# BackupPowerSupply.net
KiCad netlist of a schematic drawn in EAGLE
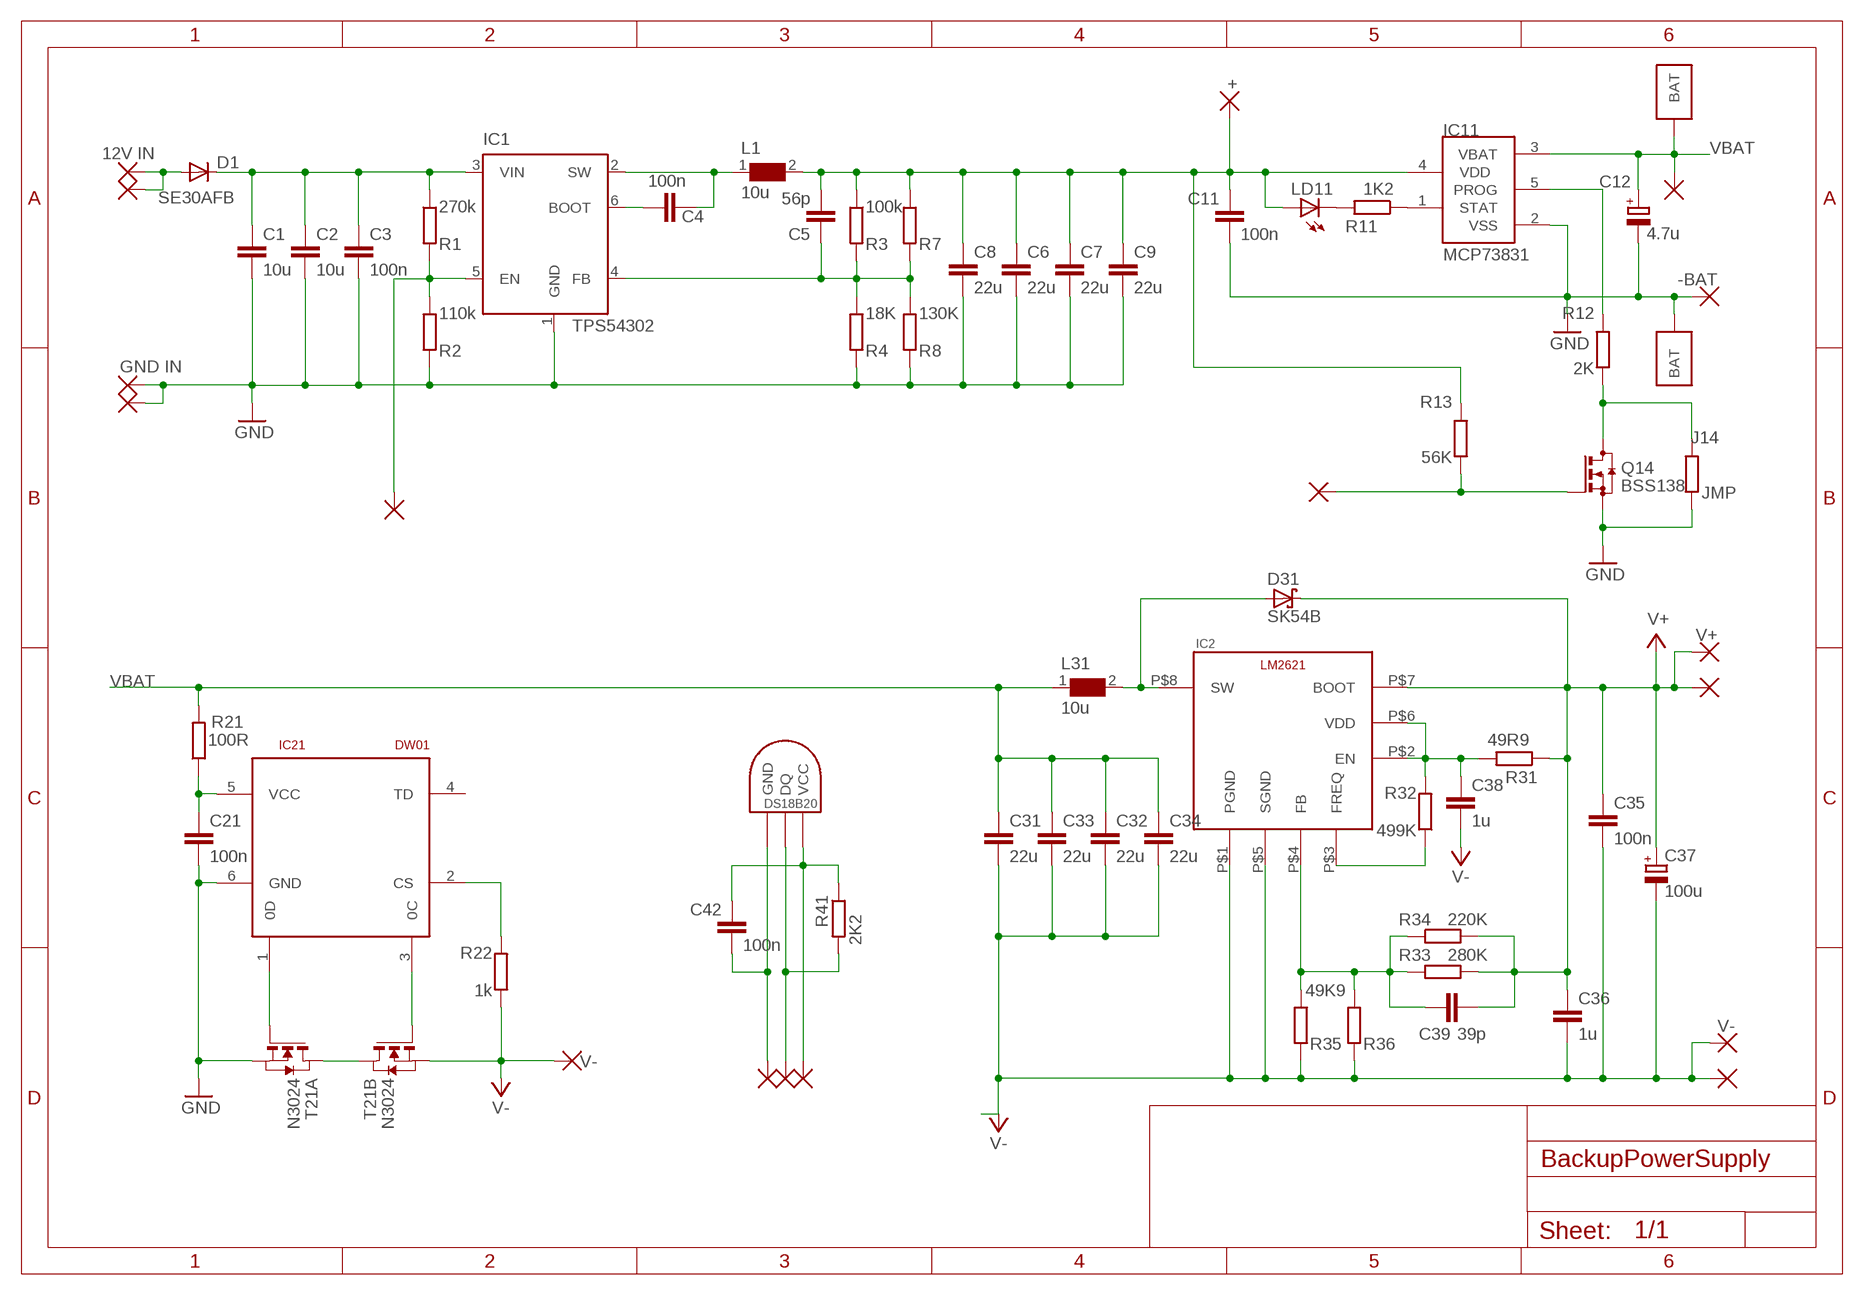
[diagram p0: schematic, sheet 1]

(export (version "E")
  (design (tool "Eeschema 10.0.6"))
  (components
    (comp (ref "C1")
      (value "10u")
      (footprint "eagle-import:C1206")
      (libsource (lib "eagle-import") (part "C-EUC1206"))
    )
    (comp (ref "C2")
      (value "10u")
      (footprint "eagle-import:C1206")
      (libsource (lib "eagle-import") (part "C-EUC1206"))
    )
    (comp (ref "C3")
      (value "100n")
      (footprint "eagle-import:C1206")
      (libsource (lib "eagle-import") (part "C-EUC1206"))
    )
    (comp (ref "C4")
      (value "100n")
      (footprint "eagle-import:C0805")
      (libsource (lib "eagle-import") (part "C-EUC0805"))
    )
    (comp (ref "C5")
      (value "56p")
      (footprint "eagle-import:C0805")
      (libsource (lib "eagle-import") (part "C-EUC0805"))
    )
    (comp (ref "C6")
      (value "22u")
      (footprint "eagle-import:C0805")
      (libsource (lib "eagle-import") (part "C-EUC0805"))
    )
    (comp (ref "C7")
      (value "22u")
      (footprint "eagle-import:C0805")
      (libsource (lib "eagle-import") (part "C-EUC0805"))
    )
    (comp (ref "C8")
      (value "22u")
      (footprint "eagle-import:C0805")
      (libsource (lib "eagle-import") (part "C-EUC0805"))
    )
    (comp (ref "C9")
      (value "22u")
      (footprint "eagle-import:C0805")
      (libsource (lib "eagle-import") (part "C-EUC0805"))
    )
    (comp (ref "C11")
      (value "100n")
      (footprint "eagle-import:C0805")
      (libsource (lib "eagle-import") (part "C-EUC0805"))
    )
    (comp (ref "C12")
      (value "4.7u")
      (footprint "eagle-import:SMC_A")
      (libsource (lib "eagle-import") (part "CPOL-EUSMCA"))
    )
    (comp (ref "C21")
      (value "100n")
      (footprint "eagle-import:C0805")
      (libsource (lib "eagle-import") (part "C-EUC0805"))
    )
    (comp (ref "C31")
      (value "22u")
      (footprint "eagle-import:C0805")
      (libsource (lib "eagle-import") (part "C-EUC0805"))
    )
    (comp (ref "C32")
      (value "22u")
      (footprint "eagle-import:C0805")
      (libsource (lib "eagle-import") (part "C-EUC0805"))
    )
    (comp (ref "C33")
      (value "22u")
      (footprint "eagle-import:C0805")
      (libsource (lib "eagle-import") (part "C-EUC0805"))
    )
    (comp (ref "C34")
      (value "22u")
      (footprint "eagle-import:C0805")
      (libsource (lib "eagle-import") (part "C-EUC0805"))
    )
    (comp (ref "C35")
      (value "100n")
      (footprint "eagle-import:C0805")
      (libsource (lib "eagle-import") (part "C-EUC0805"))
    )
    (comp (ref "C36")
      (value "1u")
      (footprint "eagle-import:C0805")
      (libsource (lib "eagle-import") (part "C-EUC0805"))
    )
    (comp (ref "C37")
      (value "100u")
      (footprint "eagle-import:SMC_B")
      (libsource (lib "eagle-import") (part "CPOL-EUSMCB"))
    )
    (comp (ref "C38")
      (value "1u")
      (footprint "eagle-import:C0805")
      (libsource (lib "eagle-import") (part "C-EUC0805"))
    )
    (comp (ref "C39")
      (value "39p")
      (footprint "eagle-import:C0805")
      (libsource (lib "eagle-import") (part "C-EUC0805"))
    )
    (comp (ref "C42")
      (value "100n")
      (footprint "eagle-import:C0603")
      (libsource (lib "eagle-import") (part "C-EUC0603"))
    )
    (comp (ref "D1")
      (value "SE30AFB")
      (footprint "eagle-import:SOD-123_MINI-SMA")
      (libsource (lib "eagle-import") (part "CGRM400-G1"))
    )
    (comp (ref "D31")
      (value "SK54B")
      (footprint "eagle-import:SMB")
      (libsource (lib "eagle-import") (part "SCHOTTKY-DIODESMD"))
    )
    (comp (ref "DS18B20")
      (value "DS1820SOIC")
      (footprint "eagle-import:DS18B20_SOIC")
      (libsource (lib "eagle-import") (part "DS1820SOIC"))
    )
    (comp (ref "IC1")
      (value "TPS54302")
      (footprint "eagle-import:TSOT23-6_DDC")
      (libsource (lib "eagle-import") (part "TPS54302"))
    )
    (comp (ref "IC2")
      (value "LM2621VSSOP8")
      (footprint "eagle-import:VSSOP8")
      (libsource (lib "eagle-import") (part "LM2621VSSOP8"))
    )
    (comp (ref "IC11")
      (value "MCP73831")
      (footprint "eagle-import:SOT23-5L")
      (libsource (lib "eagle-import") (part "MCP73831"))
    )
    (comp (ref "IC21")
      (value "DW01")
      (footprint "eagle-import:SOT23-6")
      (libsource (lib "eagle-import") (part "DW01"))
    )
    (comp (ref "J14")
      (value "JMP")
      (footprint "eagle-import:R0201")
      (libsource (lib "eagle-import") (part "R-EU_R0201"))
    )
    (comp (ref "L1")
      (value "10u")
      (footprint "eagle-import:WE-LQS_8040")
      (libsource (lib "eagle-import") (part "WE-LQS_8040"))
    )
    (comp (ref "L31")
      (value "10u")
      (footprint "eagle-import:WE-LQS_8040")
      (libsource (lib "eagle-import") (part "WE-LQS_8040"))
    )
    (comp (ref "LD11")
      (value "LEDCHIPLED_0805")
      (footprint "eagle-import:CHIPLED_0805")
      (libsource (lib "eagle-import") (part "LEDCHIPLED_0805"))
    )
    (comp (ref "PAD1")
      (value "+BAT")
      (footprint "eagle-import:PAD")
      (libsource (lib "eagle-import") (part "PAD"))
    )
    (comp (ref "PAD2")
      (value "-BAT")
      (footprint "eagle-import:PAD")
      (libsource (lib "eagle-import") (part "PAD"))
    )
    (comp (ref "PAD3")
      (value "12V IN")
      (footprint "eagle-import:PAD")
      (libsource (lib "eagle-import") (part "PAD"))
    )
    (comp (ref "PAD4")
      (value "GND IN")
      (footprint "eagle-import:PAD")
      (libsource (lib "eagle-import") (part "PAD"))
    )
    (comp (ref "PAD5")
      (value "V+")
      (footprint "eagle-import:PAD")
      (libsource (lib "eagle-import") (part "PAD"))
    )
    (comp (ref "PAD6")
      (value "V-")
      (footprint "eagle-import:PAD")
      (libsource (lib "eagle-import") (part "PAD"))
    )
    (comp (ref "PAD7")
      (value "+")
      (footprint "eagle-import:PAD")
      (libsource (lib "eagle-import") (part "PAD"))
    )
    (comp (ref "PAD8")
      (value "PAD")
      (footprint "eagle-import:PAD")
      (libsource (lib "eagle-import") (part "PAD"))
    )
    (comp (ref "PAD9")
      (value "V-")
      (footprint "eagle-import:PAD")
      (libsource (lib "eagle-import") (part "PAD"))
    )
    (comp (ref "PAD11")
      (value "V-")
      (footprint "eagle-import:PAD")
      (libsource (lib "eagle-import") (part "PAD"))
    )
    (comp (ref "PAD12")
      (value "V+")
      (footprint "eagle-import:PAD")
      (libsource (lib "eagle-import") (part "PAD"))
    )
    (comp (ref "PAD13")
      (value "+")
      (footprint "eagle-import:PAD")
      (libsource (lib "eagle-import") (part "PAD"))
    )
    (comp (ref "PAD19")
      (value "V-")
      (footprint "eagle-import:PAD")
      (libsource (lib "eagle-import") (part "PAD"))
    )
    (comp (ref "PAD20")
      (value "V-")
      (footprint "eagle-import:PAD")
      (libsource (lib "eagle-import") (part "PAD"))
    )
    (comp (ref "PAD21")
      (value "V-")
      (footprint "eagle-import:PAD")
      (libsource (lib "eagle-import") (part "PAD"))
    )
    (comp (ref "PAD22")
      (value "PAD")
      (footprint "eagle-import:PAD")
      (libsource (lib "eagle-import") (part "PAD"))
    )
    (comp (ref "Q14")
      (value "BSS138")
      (footprint "eagle-import:SOT23")
      (libsource (lib "eagle-import") (part "BSS123"))
    )
    (comp (ref "R1")
      (value "270k")
      (footprint "eagle-import:M0805")
      (libsource (lib "eagle-import") (part "R-EU_M0805"))
    )
    (comp (ref "R2")
      (value "110k")
      (footprint "eagle-import:M0805")
      (libsource (lib "eagle-import") (part "R-EU_M0805"))
    )
    (comp (ref "R3")
      (value "100k")
      (footprint "eagle-import:M0805")
      (libsource (lib "eagle-import") (part "R-EU_M0805"))
    )
    (comp (ref "R4")
      (value "18K")
      (footprint "eagle-import:M0805")
      (libsource (lib "eagle-import") (part "R-EU_M0805"))
    )
    (comp (ref "R7")
      (value "R-EU_M0805")
      (footprint "eagle-import:M0805")
      (libsource (lib "eagle-import") (part "R-EU_M0805"))
    )
    (comp (ref "R8")
      (value "130K")
      (footprint "eagle-import:M0805")
      (libsource (lib "eagle-import") (part "R-EU_M0805"))
    )
    (comp (ref "R11")
      (value "1K2")
      (footprint "eagle-import:M0805")
      (libsource (lib "eagle-import") (part "R-EU_M0805"))
    )
    (comp (ref "R12")
      (value "2K")
      (footprint "eagle-import:M0805")
      (libsource (lib "eagle-import") (part "R-EU_M0805"))
    )
    (comp (ref "R13")
      (value "56K")
      (footprint "eagle-import:M0805")
      (libsource (lib "eagle-import") (part "R-EU_M0805"))
    )
    (comp (ref "R21")
      (value "100R")
      (footprint "eagle-import:M0805")
      (libsource (lib "eagle-import") (part "R-EU_M0805"))
    )
    (comp (ref "R22")
      (value "1k")
      (footprint "eagle-import:M0805")
      (libsource (lib "eagle-import") (part "R-EU_M0805"))
    )
    (comp (ref "R31")
      (value "49R9")
      (footprint "eagle-import:M0805")
      (libsource (lib "eagle-import") (part "R-EU_M0805"))
    )
    (comp (ref "R32")
      (value "499K")
      (footprint "eagle-import:M0805")
      (libsource (lib "eagle-import") (part "R-EU_M0805"))
    )
    (comp (ref "R33")
      (value "280K")
      (footprint "eagle-import:M0805")
      (libsource (lib "eagle-import") (part "R-EU_M0805"))
    )
    (comp (ref "R34")
      (value "220K")
      (footprint "eagle-import:M0805")
      (libsource (lib "eagle-import") (part "R-EU_M0805"))
    )
    (comp (ref "R35")
      (value "49K9")
      (footprint "eagle-import:M0805")
      (libsource (lib "eagle-import") (part "R-EU_M0805"))
    )
    (comp (ref "R36")
      (value "R-EU_M0805")
      (footprint "eagle-import:M0805")
      (libsource (lib "eagle-import") (part "R-EU_M0805"))
    )
    (comp (ref "R41")
      (value "2K2")
      (footprint "eagle-import:R0603")
      (libsource (lib "eagle-import") (part "R-EU_R0603"))
    )
    (comp (ref "T21")
      (value "N3024")
      (footprint "eagle-import:TSSOP-8")
      (libsource (lib "eagle-import") (part "DMN3024LSD"))
    )
    (comp (ref "U$1")
      (value "BAT_A")
      (footprint "eagle-import:BAT_A")
      (libsource (lib "eagle-import") (part "BAT_A"))
    )
    (comp (ref "U$2")
      (value "BAT_A")
      (footprint "eagle-import:BAT_A")
      (libsource (lib "eagle-import") (part "BAT_A"))
    )
    (comp (ref "U$3")
      (value "PAD")
      (footprint "eagle-import:PAD")
      (libsource (lib "eagle-import") (part "PAD"))
    )
  )
  (nets
    (net (code "1") (name "/VBAT") (class "Default")
      (node (ref "C12") (pin "+") (pinfunction "+_+") (pintype "passive"))
      (node (ref "C31") (pin "2") (pinfunction "2_2") (pintype "passive"))
      (node (ref "C32") (pin "2") (pinfunction "2_2") (pintype "passive"))
      (node (ref "C33") (pin "2") (pinfunction "2_2") (pintype "passive"))
      (node (ref "C34") (pin "2") (pinfunction "2_2") (pintype "passive"))
      (node (ref "IC11") (pin "3") (pinfunction "VBAT_3") (pintype "bidirectional"))
      (node (ref "L31") (pin "1") (pinfunction "1_1") (pintype "passive"))
      (node (ref "PAD1") (pin "P$1") (pinfunction "P$1_P$1") (pintype "bidirectional"))
      (node (ref "R21") (pin "2") (pinfunction "2_2") (pintype "passive"))
      (node (ref "U$1") (pin "P$1") (pinfunction "BAT_P$1") (pintype "power_in"))
      (node (ref "U$1") (pin "P$4") (pinfunction "BAT_P$4") (pintype "power_in"))
    )
    (net (code "2") (name "GND") (class "Default")
      (node (ref "C1") (pin "1") (pinfunction "1_1") (pintype "passive"))
      (node (ref "C11") (pin "1") (pinfunction "1_1") (pintype "passive"))
      (node (ref "C12") (pin "-") (pinfunction "-_-") (pintype "passive"))
      (node (ref "C2") (pin "1") (pinfunction "1_1") (pintype "passive"))
      (node (ref "C21") (pin "1") (pinfunction "1_1") (pintype "passive"))
      (node (ref "C3") (pin "1") (pinfunction "1_1") (pintype "passive"))
      (node (ref "C6") (pin "1") (pinfunction "1_1") (pintype "passive"))
      (node (ref "C7") (pin "1") (pinfunction "1_1") (pintype "passive"))
      (node (ref "C8") (pin "1") (pinfunction "1_1") (pintype "passive"))
      (node (ref "C9") (pin "1") (pinfunction "1_1") (pintype "passive"))
      (node (ref "IC1") (pin "1") (pinfunction "GND_1") (pintype "power_in"))
      (node (ref "IC11") (pin "2") (pinfunction "VSS_2") (pintype "bidirectional"))
      (node (ref "IC21") (pin "6") (pinfunction "GND_6") (pintype "bidirectional"))
      (node (ref "J14") (pin "1") (pinfunction "1_1") (pintype "passive"))
      (node (ref "PAD2") (pin "P$1") (pinfunction "P$1_P$1") (pintype "bidirectional"))
      (node (ref "PAD4") (pin "P$1") (pinfunction "P$1_P$1") (pintype "bidirectional"))
      (node (ref "PAD8") (pin "P$1") (pinfunction "P$1_P$1") (pintype "bidirectional"))
      (node (ref "Q14") (pin "2") (pinfunction "S_2") (pintype "passive"))
      (node (ref "R2") (pin "2") (pinfunction "2_2") (pintype "passive"))
      (node (ref "R4") (pin "2") (pinfunction "2_2") (pintype "passive"))
      (node (ref "R8") (pin "2") (pinfunction "2_2") (pintype "passive"))
      (node (ref "T21") (pin "2") (pinfunction "S_2") (pintype "bidirectional"))
      (node (ref "T21") (pin "3") (pinfunction "S_3") (pintype "bidirectional"))
      (node (ref "U$2") (pin "P$1") (pinfunction "BAT_P$1") (pintype "power_in"))
      (node (ref "U$2") (pin "P$4") (pinfunction "BAT_P$4") (pintype "power_in"))
    )
    (net (code "3") (name "Net-(C42-Pad1)") (class "Default")
      (node (ref "C42") (pin "1") (pinfunction "1_1") (pintype "passive"))
      (node (ref "DS18B20") (pin "GND") (pinfunction "GND_GND") (pintype "power_in"))
      (node (ref "PAD21") (pin "P$1") (pinfunction "P$1_P$1") (pintype "bidirectional"))
    )
    (net (code "4") (name "Net-(C42-Pad2)") (class "Default")
      (node (ref "C42") (pin "2") (pinfunction "2_2") (pintype "passive"))
      (node (ref "DS18B20") (pin "VCC") (pinfunction "VCC_VCC") (pintype "power_in"))
      (node (ref "PAD20") (pin "P$1") (pinfunction "P$1_P$1") (pintype "bidirectional"))
      (node (ref "R41") (pin "1") (pinfunction "1_1") (pintype "passive"))
    )
    (net (code "5") (name "Net-(D1-PadA)") (class "Default")
      (node (ref "D1") (pin "A") (pinfunction "A_A") (pintype "passive"))
      (node (ref "PAD3") (pin "P$1") (pinfunction "P$1_P$1") (pintype "bidirectional"))
      (node (ref "U$3") (pin "P$1") (pinfunction "P$1_P$1") (pintype "bidirectional"))
    )
    (net (code "6") (name "Net-(DS18B20-PadDQ)") (class "Default")
      (node (ref "DS18B20") (pin "DQ") (pinfunction "DQ_DQ") (pintype "bidirectional"))
      (node (ref "PAD19") (pin "P$1") (pinfunction "P$1_P$1") (pintype "bidirectional"))
      (node (ref "R41") (pin "2") (pinfunction "2_2") (pintype "passive"))
    )
    (net (code "7") (name "Net-(IC1-BOOT)") (class "Default")
      (node (ref "C4") (pin "2") (pinfunction "2_2") (pintype "passive"))
      (node (ref "IC1") (pin "6") (pinfunction "BOOT_6") (pintype "output"))
    )
    (net (code "8") (name "Net-(IC1-EN)") (class "Default")
      (node (ref "IC1") (pin "5") (pinfunction "EN_5") (pintype "power_in"))
      (node (ref "PAD22") (pin "P$1") (pinfunction "P$1_P$1") (pintype "bidirectional"))
      (node (ref "R1") (pin "2") (pinfunction "2_2") (pintype "passive"))
      (node (ref "R2") (pin "1") (pinfunction "1_1") (pintype "passive"))
    )
    (net (code "9") (name "Net-(IC1-FB)") (class "Default")
      (node (ref "C5") (pin "2") (pinfunction "2_2") (pintype "passive"))
      (node (ref "IC1") (pin "4") (pinfunction "FB_4") (pintype "input"))
      (node (ref "R3") (pin "2") (pinfunction "2_2") (pintype "passive"))
      (node (ref "R4") (pin "1") (pinfunction "1_1") (pintype "passive"))
      (node (ref "R7") (pin "2") (pinfunction "2_2") (pintype "passive"))
      (node (ref "R8") (pin "1") (pinfunction "1_1") (pintype "passive"))
    )
    (net (code "10") (name "Net-(IC1-SW)") (class "Default")
      (node (ref "C4") (pin "1") (pinfunction "1_1") (pintype "passive"))
      (node (ref "IC1") (pin "2") (pinfunction "SW_2") (pintype "input"))
      (node (ref "L1") (pin "1") (pinfunction "1_1") (pintype "passive"))
    )
    (net (code "11") (name "Net-(IC1-VIN)") (class "Default")
      (node (ref "C1") (pin "2") (pinfunction "2_2") (pintype "passive"))
      (node (ref "C2") (pin "2") (pinfunction "2_2") (pintype "passive"))
      (node (ref "C3") (pin "2") (pinfunction "2_2") (pintype "passive"))
      (node (ref "D1") (pin "C") (pinfunction "C_C") (pintype "passive"))
      (node (ref "IC1") (pin "3") (pinfunction "VIN_3") (pintype "power_in"))
      (node (ref "R1") (pin "1") (pinfunction "1_1") (pintype "passive"))
    )
    (net (code "12") (name "Net-(IC2-EN)") (class "Default")
      (node (ref "C38") (pin "2") (pinfunction "2_2") (pintype "passive"))
      (node (ref "IC2") (pin "P$2") (pinfunction "EN_P$2") (pintype "bidirectional"))
      (node (ref "IC2") (pin "P$6") (pinfunction "VDD_P$6") (pintype "bidirectional"))
      (node (ref "R31") (pin "2") (pinfunction "2_2") (pintype "passive"))
      (node (ref "R32") (pin "2") (pinfunction "2_2") (pintype "passive"))
    )
    (net (code "13") (name "Net-(IC2-FB)") (class "Default")
      (node (ref "C39") (pin "1") (pinfunction "1_1") (pintype "passive"))
      (node (ref "IC2") (pin "P$4") (pinfunction "FB_P$4") (pintype "bidirectional"))
      (node (ref "R33") (pin "1") (pinfunction "1_1") (pintype "passive"))
      (node (ref "R34") (pin "1") (pinfunction "1_1") (pintype "passive"))
      (node (ref "R35") (pin "1") (pinfunction "1_1") (pintype "passive"))
      (node (ref "R36") (pin "1") (pinfunction "1_1") (pintype "passive"))
    )
    (net (code "14") (name "Net-(IC2-FREQ)") (class "Default")
      (node (ref "IC2") (pin "P$3") (pinfunction "FREQ_P$3") (pintype "bidirectional"))
      (node (ref "R32") (pin "1") (pinfunction "1_1") (pintype "passive"))
    )
    (net (code "15") (name "Net-(IC2-SW)") (class "Default")
      (node (ref "D31") (pin "A") (pinfunction "A_A") (pintype "passive"))
      (node (ref "IC2") (pin "P$8") (pinfunction "SW_P$8") (pintype "bidirectional"))
      (node (ref "L31") (pin "2") (pinfunction "2_2") (pintype "passive"))
    )
    (net (code "16") (name "Net-(IC11-PROG)") (class "Default")
      (node (ref "IC11") (pin "5") (pinfunction "PROG_5") (pintype "bidirectional"))
      (node (ref "R12") (pin "2") (pinfunction "2_2") (pintype "passive"))
    )
    (net (code "17") (name "Net-(IC11-STAT)") (class "Default")
      (node (ref "IC11") (pin "1") (pinfunction "STAT_1") (pintype "bidirectional"))
      (node (ref "R11") (pin "1") (pinfunction "1_1") (pintype "passive"))
    )
    (net (code "18") (name "Net-(IC11-VDD)") (class "Default")
      (node (ref "C11") (pin "2") (pinfunction "2_2") (pintype "passive"))
      (node (ref "C5") (pin "1") (pinfunction "1_1") (pintype "passive"))
      (node (ref "C6") (pin "2") (pinfunction "2_2") (pintype "passive"))
      (node (ref "C7") (pin "2") (pinfunction "2_2") (pintype "passive"))
      (node (ref "C8") (pin "2") (pinfunction "2_2") (pintype "passive"))
      (node (ref "C9") (pin "2") (pinfunction "2_2") (pintype "passive"))
      (node (ref "IC11") (pin "4") (pinfunction "VDD_4") (pintype "bidirectional"))
      (node (ref "L1") (pin "2") (pinfunction "2_2") (pintype "passive"))
      (node (ref "LD11") (pin "A") (pinfunction "A_A") (pintype "passive"))
      (node (ref "PAD13") (pin "P$1") (pinfunction "P$1_P$1") (pintype "bidirectional"))
      (node (ref "R13") (pin "2") (pinfunction "2_2") (pintype "passive"))
      (node (ref "R3") (pin "1") (pinfunction "1_1") (pintype "passive"))
      (node (ref "R7") (pin "1") (pinfunction "1_1") (pintype "passive"))
    )
    (net (code "19") (name "Net-(IC21-0C)") (class "Default")
      (node (ref "IC21") (pin "3") (pinfunction "0C_3") (pintype "bidirectional"))
      (node (ref "T21") (pin "5") (pinfunction "G_5") (pintype "bidirectional"))
    )
    (net (code "20") (name "Net-(IC21-0D)") (class "Default")
      (node (ref "IC21") (pin "1") (pinfunction "0D_1") (pintype "bidirectional"))
      (node (ref "T21") (pin "4") (pinfunction "G_4") (pintype "bidirectional"))
    )
    (net (code "21") (name "Net-(IC21-CS)") (class "Default")
      (node (ref "IC21") (pin "2") (pinfunction "CS_2") (pintype "bidirectional"))
      (node (ref "R22") (pin "2") (pinfunction "2_2") (pintype "passive"))
    )
    (net (code "22") (name "Net-(IC21-VCC)") (class "Default")
      (node (ref "C21") (pin "2") (pinfunction "2_2") (pintype "passive"))
      (node (ref "IC21") (pin "5") (pinfunction "VCC_5") (pintype "bidirectional"))
      (node (ref "R21") (pin "1") (pinfunction "1_1") (pintype "passive"))
    )
    (net (code "23") (name "Net-(LD11-PadC)") (class "Default")
      (node (ref "LD11") (pin "C") (pinfunction "C_C") (pintype "passive"))
      (node (ref "R11") (pin "2") (pinfunction "2_2") (pintype "passive"))
    )
    (net (code "24") (name "Net-(Q14-D)") (class "Default")
      (node (ref "J14") (pin "2") (pinfunction "2_2") (pintype "passive"))
      (node (ref "Q14") (pin "3") (pinfunction "D_3") (pintype "passive"))
      (node (ref "R12") (pin "1") (pinfunction "1_1") (pintype "passive"))
    )
    (net (code "25") (name "Net-(Q14-G)") (class "Default")
      (node (ref "PAD7") (pin "P$1") (pinfunction "P$1_P$1") (pintype "bidirectional"))
      (node (ref "Q14") (pin "1") (pinfunction "G_1") (pintype "passive"))
      (node (ref "R13") (pin "1") (pinfunction "1_1") (pintype "passive"))
    )
    (net (code "26") (name "Net-(T21A-D)") (class "Default")
      (node (ref "T21") (pin "1") (pinfunction "D_1") (pintype "bidirectional"))
      (node (ref "T21") (pin "8") (pinfunction "D_8") (pintype "bidirectional"))
    )
    (net (code "27") (name "V+") (class "Default")
      (node (ref "C35") (pin "2") (pinfunction "2_2") (pintype "passive"))
      (node (ref "C36") (pin "2") (pinfunction "2_2") (pintype "passive"))
      (node (ref "C37") (pin "+") (pinfunction "+_+") (pintype "passive"))
      (node (ref "C39") (pin "2") (pinfunction "2_2") (pintype "passive"))
      (node (ref "D31") (pin "C") (pinfunction "C_C") (pintype "passive"))
      (node (ref "IC2") (pin "P$7") (pinfunction "BOOT_P$7") (pintype "bidirectional"))
      (node (ref "PAD12") (pin "P$1") (pinfunction "P$1_P$1") (pintype "bidirectional"))
      (node (ref "PAD5") (pin "P$1") (pinfunction "P$1_P$1") (pintype "bidirectional"))
      (node (ref "R31") (pin "1") (pinfunction "1_1") (pintype "passive"))
      (node (ref "R33") (pin "2") (pinfunction "2_2") (pintype "passive"))
      (node (ref "R34") (pin "2") (pinfunction "2_2") (pintype "passive"))
    )
    (net (code "28") (name "V-") (class "Default")
      (node (ref "C31") (pin "1") (pinfunction "1_1") (pintype "passive"))
      (node (ref "C32") (pin "1") (pinfunction "1_1") (pintype "passive"))
      (node (ref "C33") (pin "1") (pinfunction "1_1") (pintype "passive"))
      (node (ref "C34") (pin "1") (pinfunction "1_1") (pintype "passive"))
      (node (ref "C35") (pin "1") (pinfunction "1_1") (pintype "passive"))
      (node (ref "C36") (pin "1") (pinfunction "1_1") (pintype "passive"))
      (node (ref "C37") (pin "-") (pinfunction "-_-") (pintype "passive"))
      (node (ref "C38") (pin "1") (pinfunction "1_1") (pintype "passive"))
      (node (ref "IC2") (pin "P$1") (pinfunction "PGND_P$1") (pintype "bidirectional"))
      (node (ref "IC2") (pin "P$5") (pinfunction "SGND_P$5") (pintype "bidirectional"))
      (node (ref "PAD11") (pin "P$1") (pinfunction "P$1_P$1") (pintype "bidirectional"))
      (node (ref "PAD6") (pin "P$1") (pinfunction "P$1_P$1") (pintype "bidirectional"))
      (node (ref "PAD9") (pin "P$1") (pinfunction "P$1_P$1") (pintype "bidirectional"))
      (node (ref "R22") (pin "1") (pinfunction "1_1") (pintype "passive"))
      (node (ref "R35") (pin "2") (pinfunction "2_2") (pintype "passive"))
      (node (ref "R36") (pin "2") (pinfunction "2_2") (pintype "passive"))
      (node (ref "T21") (pin "6") (pinfunction "S_6") (pintype "bidirectional"))
      (node (ref "T21") (pin "7") (pinfunction "S_7") (pintype "bidirectional"))
    )
    (net (code "29") (name "unconnected-(IC21-TD-Pad4)") (class "Default")
      (node (ref "IC21") (pin "4") (pinfunction "TD_4") (pintype "bidirectional"))
    )
  )
)
